# heater_motor.net
KiCad netlist of a schematic drawn in EAGLE
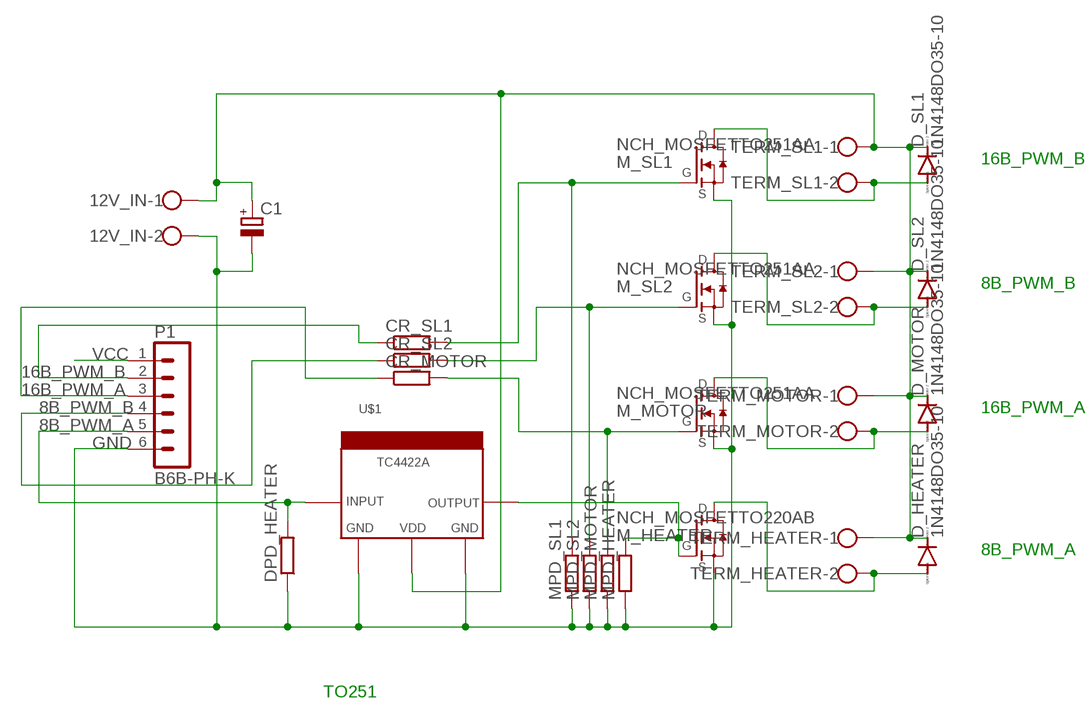
[diagram p0: schematic, sheet 1]

(export (version "E")
  (design (tool "Eeschema 10.0.6"))
  (components
    (comp (ref "12V_IN")
      (value "W237-102")
      (footprint "eagle-import:W237-102")
      (fields (field (name "MPN") "237-102"))
      (libsource (lib "eagle-import") (part "W237-102"))
    )
    (comp (ref "C1")
      (value "CPOL-EUE5-10.5")
      (footprint "eagle-import:E5-10,5")
      (libsource (lib "eagle-import") (part "CPOL-EUE5-10.5"))
    )
    (comp (ref "CR_MOTOR")
      (value "R-EU_0207/10")
      (footprint "eagle-import:0207_10")
      (libsource (lib "eagle-import") (part "R-EU_0207/10"))
    )
    (comp (ref "CR_SL1")
      (value "R-EU_0207/10")
      (footprint "eagle-import:0207_10")
      (libsource (lib "eagle-import") (part "R-EU_0207/10"))
    )
    (comp (ref "CR_SL2")
      (value "R-EU_0207/10")
      (footprint "eagle-import:0207_10")
      (libsource (lib "eagle-import") (part "R-EU_0207/10"))
    )
    (comp (ref "DPD_HEATER")
      (value "R-EU_0207/10")
      (footprint "eagle-import:0207_10")
      (libsource (lib "eagle-import") (part "R-EU_0207/10"))
    )
    (comp (ref "D_HEATER")
      (value "1N4148DO35-10")
      (footprint "eagle-import:DO35-10")
      (libsource (lib "eagle-import") (part "1N4148DO35-10"))
    )
    (comp (ref "D_MOTOR")
      (value "1N4148DO35-10")
      (footprint "eagle-import:DO35-10")
      (libsource (lib "eagle-import") (part "1N4148DO35-10"))
    )
    (comp (ref "D_SL1")
      (value "1N4148DO35-10")
      (footprint "eagle-import:DO35-10")
      (libsource (lib "eagle-import") (part "1N4148DO35-10"))
    )
    (comp (ref "D_SL2")
      (value "1N4148DO35-10")
      (footprint "eagle-import:DO35-10")
      (libsource (lib "eagle-import") (part "1N4148DO35-10"))
    )
    (comp (ref "MPD_HEATER")
      (value "R-EU_0207/10")
      (footprint "eagle-import:0207_10")
      (libsource (lib "eagle-import") (part "R-EU_0207/10"))
    )
    (comp (ref "MPD_MOTOR")
      (value "R-EU_0207/10")
      (footprint "eagle-import:0207_10")
      (libsource (lib "eagle-import") (part "R-EU_0207/10"))
    )
    (comp (ref "MPD_SL1")
      (value "R-EU_0207/10")
      (footprint "eagle-import:0207_10")
      (libsource (lib "eagle-import") (part "R-EU_0207/10"))
    )
    (comp (ref "MPD_SL2")
      (value "R-EU_0207/10")
      (footprint "eagle-import:0207_10")
      (libsource (lib "eagle-import") (part "R-EU_0207/10"))
    )
    (comp (ref "M_HEATER")
      (value "NCH_MOSFETTO220AB")
      (footprint "eagle-import:TO220AB")
      (libsource (lib "eagle-import") (part "NCH_MOSFETTO220AB"))
    )
    (comp (ref "M_MOTOR")
      (value "NCH_MOSFETTO251AA")
      (footprint "eagle-import:TO251AA")
      (libsource (lib "eagle-import") (part "NCH_MOSFETTO251AA"))
    )
    (comp (ref "M_SL1")
      (value "NCH_MOSFETTO251AA")
      (footprint "eagle-import:TO251AA")
      (libsource (lib "eagle-import") (part "NCH_MOSFETTO251AA"))
    )
    (comp (ref "M_SL2")
      (value "NCH_MOSFETTO251AA")
      (footprint "eagle-import:TO251AA")
      (libsource (lib "eagle-import") (part "NCH_MOSFETTO251AA"))
    )
    (comp (ref "P1")
      (value "B6B-PH-K")
      (footprint "eagle-import:B6B-PH-K")
      (libsource (lib "eagle-import") (part "B6B-PH-K"))
    )
    (comp (ref "TERM_HEATER")
      (value "W237-102")
      (footprint "eagle-import:W237-102")
      (fields (field (name "MPN") "237-102"))
      (libsource (lib "eagle-import") (part "W237-102"))
    )
    (comp (ref "TERM_MOTOR")
      (value "W237-102")
      (footprint "eagle-import:W237-102")
      (fields (field (name "MPN") "237-102"))
      (libsource (lib "eagle-import") (part "W237-102"))
    )
    (comp (ref "TERM_SL1")
      (value "W237-102")
      (footprint "eagle-import:W237-102")
      (fields (field (name "MPN") "237-102"))
      (libsource (lib "eagle-import") (part "W237-102"))
    )
    (comp (ref "TERM_SL2")
      (value "W237-102")
      (footprint "eagle-import:W237-102")
      (fields (field (name "MPN") "237-102"))
      (libsource (lib "eagle-import") (part "W237-102"))
    )
    (comp (ref "U$1")
      (value "TC4422ASPACE_LEGS")
      (footprint "eagle-import:TO220-52")
      (libsource (lib "eagle-import") (part "TC4422ASPACE_LEGS"))
    )
  )
  (nets
    (net (code "1") (name "/8B_PWM_A") (class "Default")
      (node (ref "DPD_HEATER") (pin "2") (pinfunction "2_2") (pintype "passive"))
      (node (ref "P1") (pin "5") (pinfunction "5_5") (pintype "passive"))
      (node (ref "U$1") (pin "1") (pinfunction "INPUT_1") (pintype "input"))
    )
    (net (code "2") (name "/8B_PWM_B") (class "Default")
      (node (ref "CR_SL2") (pin "1") (pinfunction "1_1") (pintype "passive"))
      (node (ref "P1") (pin "4") (pinfunction "4_4") (pintype "passive"))
    )
    (net (code "3") (name "/16B_PWM_A") (class "Default")
      (node (ref "CR_MOTOR") (pin "1") (pinfunction "1_1") (pintype "passive"))
      (node (ref "P1") (pin "3") (pinfunction "3_3") (pintype "passive"))
    )
    (net (code "4") (name "/16B_PWM_B") (class "Default")
      (node (ref "CR_SL1") (pin "1") (pinfunction "1_1") (pintype "passive"))
      (node (ref "P1") (pin "2") (pinfunction "2_2") (pintype "passive"))
    )
    (net (code "5") (name "/GND") (class "Default")
      (node (ref "12V_IN") (pin "2") (pinfunction "KL_2") (pintype "passive"))
      (node (ref "C1") (pin "-") (pinfunction "-_-") (pintype "passive"))
      (node (ref "DPD_HEATER") (pin "1") (pinfunction "1_1") (pintype "passive"))
      (node (ref "MPD_HEATER") (pin "1") (pinfunction "1_1") (pintype "passive"))
      (node (ref "MPD_MOTOR") (pin "1") (pinfunction "1_1") (pintype "passive"))
      (node (ref "MPD_SL1") (pin "1") (pinfunction "1_1") (pintype "passive"))
      (node (ref "MPD_SL2") (pin "1") (pinfunction "1_1") (pintype "passive"))
      (node (ref "M_HEATER") (pin "3") (pinfunction "S_3") (pintype "passive"))
      (node (ref "M_MOTOR") (pin "3") (pinfunction "S_3") (pintype "passive"))
      (node (ref "M_SL1") (pin "3") (pinfunction "S_3") (pintype "passive"))
      (node (ref "M_SL2") (pin "3") (pinfunction "S_3") (pintype "passive"))
      (node (ref "P1") (pin "6") (pinfunction "6_6") (pintype "passive"))
      (node (ref "U$1") (pin "2") (pinfunction "GND1_2") (pintype "power_in"))
      (node (ref "U$1") (pin "4") (pinfunction "GND2_4") (pintype "power_in"))
    )
    (net (code "6") (name "/VCC") (class "Default")
      (node (ref "P1") (pin "1") (pinfunction "1_1") (pintype "passive"))
    )
    (net (code "7") (name "Net-(12V_INA-KL)") (class "Default")
      (node (ref "12V_IN") (pin "1") (pinfunction "KL_1") (pintype "passive"))
      (node (ref "C1") (pin "+") (pinfunction "+_+") (pintype "passive"))
      (node (ref "D_HEATER") (pin "C") (pinfunction "C_C") (pintype "passive"))
      (node (ref "D_MOTOR") (pin "C") (pinfunction "C_C") (pintype "passive"))
      (node (ref "D_SL1") (pin "C") (pinfunction "C_C") (pintype "passive"))
      (node (ref "D_SL2") (pin "C") (pinfunction "C_C") (pintype "passive"))
      (node (ref "TERM_HEATER") (pin "1") (pinfunction "KL_1") (pintype "passive"))
      (node (ref "TERM_MOTOR") (pin "1") (pinfunction "KL_1") (pintype "passive"))
      (node (ref "TERM_SL1") (pin "1") (pinfunction "KL_1") (pintype "passive"))
      (node (ref "TERM_SL2") (pin "1") (pinfunction "KL_1") (pintype "passive"))
      (node (ref "U$1") (pin "3") (pinfunction "VDD_3") (pintype "power_in"))
    )
    (net (code "8") (name "Net-(M_HEATER-D)") (class "Default")
      (node (ref "D_HEATER") (pin "A") (pinfunction "A_A") (pintype "passive"))
      (node (ref "M_HEATER") (pin "2") (pinfunction "D_2") (pintype "passive"))
      (node (ref "TERM_HEATER") (pin "2") (pinfunction "KL_2") (pintype "passive"))
    )
    (net (code "9") (name "Net-(M_HEATER-G)") (class "Default")
      (node (ref "MPD_HEATER") (pin "2") (pinfunction "2_2") (pintype "passive"))
      (node (ref "M_HEATER") (pin "1") (pinfunction "G_1") (pintype "passive"))
      (node (ref "U$1") (pin "5") (pinfunction "OUTPUT_5") (pintype "output"))
    )
    (net (code "10") (name "Net-(M_MOTOR-D)") (class "Default")
      (node (ref "D_MOTOR") (pin "A") (pinfunction "A_A") (pintype "passive"))
      (node (ref "M_MOTOR") (pin "2") (pinfunction "D_2") (pintype "passive"))
      (node (ref "TERM_MOTOR") (pin "2") (pinfunction "KL_2") (pintype "passive"))
    )
    (net (code "11") (name "Net-(M_MOTOR-G)") (class "Default")
      (node (ref "CR_MOTOR") (pin "2") (pinfunction "2_2") (pintype "passive"))
      (node (ref "MPD_MOTOR") (pin "2") (pinfunction "2_2") (pintype "passive"))
      (node (ref "M_MOTOR") (pin "1") (pinfunction "G_1") (pintype "passive"))
    )
    (net (code "12") (name "Net-(M_SL1-D)") (class "Default")
      (node (ref "D_SL1") (pin "A") (pinfunction "A_A") (pintype "passive"))
      (node (ref "M_SL1") (pin "2") (pinfunction "D_2") (pintype "passive"))
      (node (ref "TERM_SL1") (pin "2") (pinfunction "KL_2") (pintype "passive"))
    )
    (net (code "13") (name "Net-(M_SL1-G)") (class "Default")
      (node (ref "CR_SL1") (pin "2") (pinfunction "2_2") (pintype "passive"))
      (node (ref "MPD_SL1") (pin "2") (pinfunction "2_2") (pintype "passive"))
      (node (ref "M_SL1") (pin "1") (pinfunction "G_1") (pintype "passive"))
    )
    (net (code "14") (name "Net-(M_SL2-D)") (class "Default")
      (node (ref "D_SL2") (pin "A") (pinfunction "A_A") (pintype "passive"))
      (node (ref "M_SL2") (pin "2") (pinfunction "D_2") (pintype "passive"))
      (node (ref "TERM_SL2") (pin "2") (pinfunction "KL_2") (pintype "passive"))
    )
    (net (code "15") (name "Net-(M_SL2-G)") (class "Default")
      (node (ref "CR_SL2") (pin "2") (pinfunction "2_2") (pintype "passive"))
      (node (ref "MPD_SL2") (pin "2") (pinfunction "2_2") (pintype "passive"))
      (node (ref "M_SL2") (pin "1") (pinfunction "G_1") (pintype "passive"))
    )
  )
)
